# Juglans.net
KiCad netlist of a schematic drawn in Altium Designer
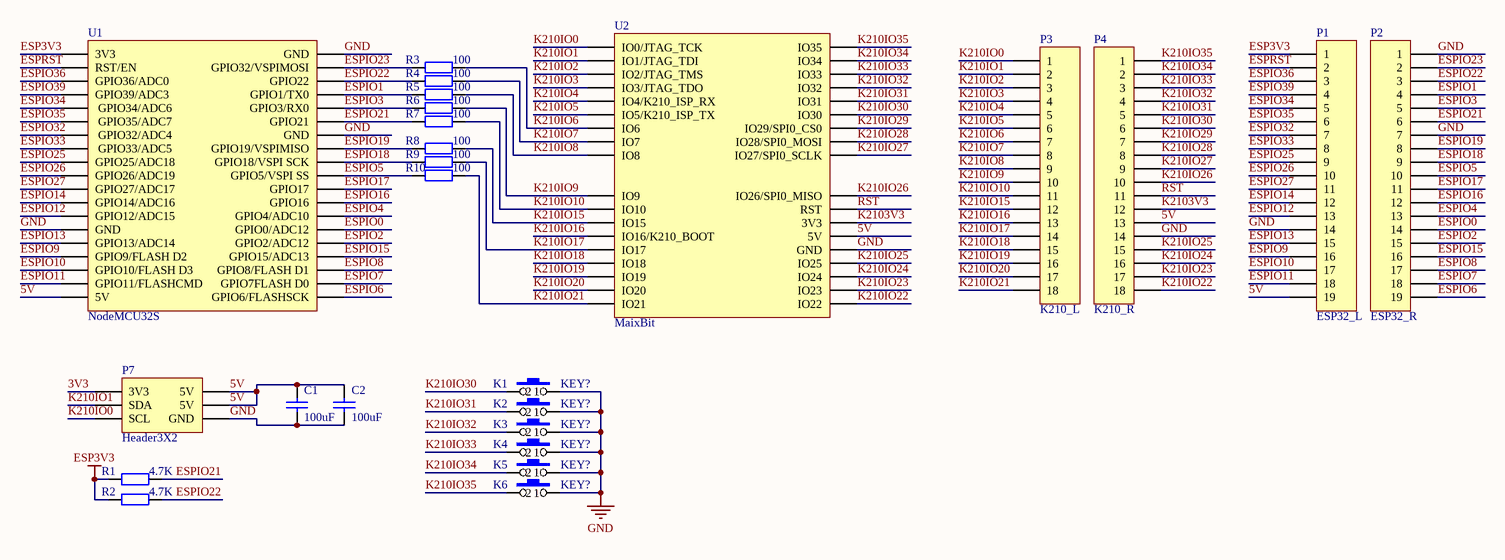
[diagram p0: Juglans.SchDoc]

(export (version "E")
  (design (tool "Eeschema 10.0.6"))
  (components
    (comp (ref "C1")
      (value "100uF")
      (footprint "C 1206_L")
      (description "Capacitor")
      (fields (field (name "Comment") "Cap") (field (name "PUBLISHER") "Altium Limited"))
      (libsource (lib "Miscellaneous Devices") (part "Cap"))
    )
    (comp (ref "C2")
      (value "100uF")
      (footprint "C 1206_L")
      (description "Capacitor")
      (fields (field (name "Comment") "Cap") (field (name "PUBLISHER") "Altium Limited"))
      (libsource (lib "Miscellaneous Devices") (part "Cap"))
    )
    (comp (ref "K1") (value "KEY?") (footprint "SW-PB2-S") (libsource (lib "Connectors") (part "SW-PB2")))
    (comp (ref "K2") (value "KEY?") (footprint "SW-PB2-S") (libsource (lib "Connectors") (part "SW-PB2")))
    (comp (ref "K3") (value "KEY?") (footprint "SW-PB2-S") (libsource (lib "Connectors") (part "SW-PB2")))
    (comp (ref "K4") (value "KEY?") (footprint "SW-PB2-S") (libsource (lib "Connectors") (part "SW-PB2")))
    (comp (ref "K5") (value "KEY?") (footprint "SW-PB2-S") (libsource (lib "Connectors") (part "SW-PB2")))
    (comp (ref "K6") (value "KEY?") (footprint "SW-PB2-S") (libsource (lib "Connectors") (part "SW-PB2")))
    (comp (ref "P1")
      (value "ESP32_L")
      (footprint "HDR1X19")
      (description "Header, 19-Pin")
      (fields (field (name "PUBLISHER") "Altium Limited"))
      (libsource (lib "") (part "Header 19_1"))
    )
    (comp (ref "P2")
      (value "ESP32_R")
      (footprint "HDR1X19")
      (description "Header, 19-Pin")
      (fields (field (name "PUBLISHER") "Altium Limited"))
      (libsource (lib "Miscellaneous Connectors") (part "Header 19"))
    )
    (comp (ref "P3")
      (value "K210_L")
      (footprint "HDR1X18")
      (description "Header, 18-Pin")
      (fields (field (name "PUBLISHER") "Altium Limited"))
      (libsource (lib "Miscellaneous Connectors") (part "Header 18"))
    )
    (comp (ref "P4")
      (value "K210_R")
      (footprint "HDR1X18")
      (description "Header, 18-Pin")
      (fields (field (name "PUBLISHER") "Altium Limited"))
      (libsource (lib "") (part "Header 18_1"))
    )
    (comp (ref "P7") (value "Header3X2") (footprint "Header3X2") (libsource (lib "Juglans") (part "H3X2")))
    (comp (ref "R1")
      (value "4.7K")
      (footprint "R 0805_M")
      (description "Resistor")
      (fields (field (name "Comment") "Res2") (field (name "PUBLISHER") "Altium Limited"))
      (libsource (lib "Miscellaneous Devices") (part "Res2"))
    )
    (comp (ref "R2")
      (value "4.7K")
      (footprint "R 0805_M")
      (description "Resistor")
      (fields (field (name "Comment") "Res2") (field (name "PUBLISHER") "Altium Limited"))
      (libsource (lib "Miscellaneous Devices") (part "Res2"))
    )
    (comp (ref "R3")
      (value "100")
      (footprint "R 0805_M")
      (description "Resistor")
      (fields (field (name "Comment") "Res2") (field (name "PUBLISHER") "Altium Limited"))
      (libsource (lib "Miscellaneous Devices") (part "Res2"))
    )
    (comp (ref "R4")
      (value "100")
      (footprint "R 0805_M")
      (description "Resistor")
      (fields (field (name "Comment") "Res2") (field (name "PUBLISHER") "Altium Limited"))
      (libsource (lib "Miscellaneous Devices") (part "Res2"))
    )
    (comp (ref "R5")
      (value "100")
      (footprint "R 0805_M")
      (description "Resistor")
      (fields (field (name "Comment") "Res2") (field (name "PUBLISHER") "Altium Limited"))
      (libsource (lib "Miscellaneous Devices") (part "Res2"))
    )
    (comp (ref "R6")
      (value "100")
      (footprint "R 0805_M")
      (description "Resistor")
      (fields (field (name "Comment") "Res2") (field (name "PUBLISHER") "Altium Limited"))
      (libsource (lib "Miscellaneous Devices") (part "Res2"))
    )
    (comp (ref "R7")
      (value "100")
      (footprint "R 0805_M")
      (description "Resistor")
      (fields (field (name "Comment") "Res2") (field (name "PUBLISHER") "Altium Limited"))
      (libsource (lib "Miscellaneous Devices") (part "Res2"))
    )
    (comp (ref "R8")
      (value "100")
      (footprint "R 0805_M")
      (description "Resistor")
      (fields (field (name "Comment") "Res2") (field (name "PUBLISHER") "Altium Limited"))
      (libsource (lib "Miscellaneous Devices") (part "Res2"))
    )
    (comp (ref "R9")
      (value "100")
      (footprint "R 0805_M")
      (description "Resistor")
      (fields (field (name "Comment") "Res2") (field (name "PUBLISHER") "Altium Limited"))
      (libsource (lib "Miscellaneous Devices") (part "Res2"))
    )
    (comp (ref "R10")
      (value "100")
      (footprint "R 0805_M")
      (description "Resistor")
      (fields (field (name "Comment") "Res2") (field (name "PUBLISHER") "Altium Limited"))
      (libsource (lib "Miscellaneous Devices") (part "Res2"))
    )
    (comp (ref "U1")
      (value "NodeMCU32S")
      (footprint "NodeMCU32S")
      (libsource (lib "Juglans") (part "NodeMCU32S"))
    )
    (comp (ref "U2") (value "MaixBit") (footprint "MaixBit") (libsource (lib "Juglans") (part "MaixBit")))
  )
  (nets
    (net (code "1") (name "/3V3") (class "Default")
      (node (ref "P7") (pin "1") (pinfunction "3V3_1") (pintype "passive"))
    )
    (net (code "2") (name "/5V") (class "Default")
      (node (ref "C1") (pin "2") (pinfunction "2_2") (pintype "passive"))
      (node (ref "C2") (pin "2") (pinfunction "2_2") (pintype "passive"))
      (node (ref "P1") (pin "19") (pinfunction "19_19") (pintype "passive"))
      (node (ref "P4") (pin "13") (pinfunction "13_13") (pintype "passive"))
      (node (ref "P7") (pin "2") (pinfunction "5V_2") (pintype "passive"))
      (node (ref "P7") (pin "4") (pinfunction "5V_4") (pintype "passive"))
      (node (ref "U1") (pin "18") (pinfunction "5V_18") (pintype "passive"))
      (node (ref "U2") (pin "23") (pinfunction "5V_23") (pintype "passive"))
    )
    (net (code "3") (name "/ESPIO0") (class "Default")
      (node (ref "P2") (pin "14") (pinfunction "14_14") (pintype "passive"))
      (node (ref "U1") (pin "24") (pinfunction "GPIO0/ADC12_24") (pintype "passive"))
    )
    (net (code "4") (name "/ESPIO1") (class "Default")
      (node (ref "P2") (pin "4") (pinfunction "4_4") (pintype "passive"))
      (node (ref "R5") (pin "2") (pinfunction "2_2") (pintype "passive"))
      (node (ref "U1") (pin "34") (pinfunction "GPIO1/TX0_34") (pintype "passive"))
    )
    (net (code "5") (name "/ESPIO2") (class "Default")
      (node (ref "P2") (pin "15") (pinfunction "15_15") (pintype "passive"))
      (node (ref "U1") (pin "23") (pinfunction "GPIO2/ADC12_23") (pintype "passive"))
    )
    (net (code "6") (name "/ESPIO3") (class "Default")
      (node (ref "P2") (pin "5") (pinfunction "5_5") (pintype "passive"))
      (node (ref "R6") (pin "2") (pinfunction "2_2") (pintype "passive"))
      (node (ref "U1") (pin "33") (pinfunction "GPIO3/RX0_33") (pintype "passive"))
    )
    (net (code "7") (name "/ESPIO4") (class "Default")
      (node (ref "P2") (pin "13") (pinfunction "13_13") (pintype "passive"))
      (node (ref "U1") (pin "25") (pinfunction "GPIO4/ADC10_25") (pintype "passive"))
    )
    (net (code "8") (name "/ESPIO5") (class "Default")
      (node (ref "P2") (pin "10") (pinfunction "10_10") (pintype "passive"))
      (node (ref "R10") (pin "2") (pinfunction "2_2") (pintype "passive"))
      (node (ref "U1") (pin "28") (pinfunction "GPIO5/VSPI_SS_28") (pintype "passive"))
    )
    (net (code "9") (name "/ESPIO6") (class "Default")
      (node (ref "P2") (pin "19") (pinfunction "19_19") (pintype "passive"))
      (node (ref "U1") (pin "19") (pinfunction "GPIO6/FLASHSCK_19") (pintype "passive"))
    )
    (net (code "10") (name "/ESPIO7") (class "Default")
      (node (ref "P2") (pin "18") (pinfunction "18_18") (pintype "passive"))
      (node (ref "U1") (pin "20") (pinfunction "GPIO7FLASH_D0_20") (pintype "passive"))
    )
    (net (code "11") (name "/ESPIO8") (class "Default")
      (node (ref "P2") (pin "17") (pinfunction "17_17") (pintype "passive"))
      (node (ref "U1") (pin "21") (pinfunction "GPIO8/FLASH_D1_21") (pintype "passive"))
    )
    (net (code "12") (name "/ESPIO9") (class "Default")
      (node (ref "P1") (pin "16") (pinfunction "16_16") (pintype "passive"))
      (node (ref "U1") (pin "15") (pinfunction "GPIO9/FLASH_D2_15") (pintype "passive"))
    )
    (net (code "13") (name "/ESPIO10") (class "Default")
      (node (ref "P1") (pin "17") (pinfunction "17_17") (pintype "passive"))
      (node (ref "U1") (pin "16") (pinfunction "GPIO10/FLASH_D3_16") (pintype "passive"))
    )
    (net (code "14") (name "/ESPIO11") (class "Default")
      (node (ref "P1") (pin "18") (pinfunction "18_18") (pintype "passive"))
      (node (ref "U1") (pin "17") (pinfunction "GPIO11/FLASHCMD_17") (pintype "passive"))
    )
    (net (code "15") (name "/ESPIO12") (class "Default")
      (node (ref "P1") (pin "13") (pinfunction "13_13") (pintype "passive"))
      (node (ref "U1") (pin "12") (pinfunction "GPIO12/ADC15_12") (pintype "passive"))
    )
    (net (code "16") (name "/ESPIO13") (class "Default")
      (node (ref "P1") (pin "15") (pinfunction "15_15") (pintype "passive"))
      (node (ref "U1") (pin "14") (pinfunction "GPIO13/ADC14_14") (pintype "passive"))
    )
    (net (code "17") (name "/ESPIO14") (class "Default")
      (node (ref "P1") (pin "12") (pinfunction "12_12") (pintype "passive"))
      (node (ref "U1") (pin "11") (pinfunction "GPIO14/ADC16_11") (pintype "passive"))
    )
    (net (code "18") (name "/ESPIO15") (class "Default")
      (node (ref "P2") (pin "16") (pinfunction "16_16") (pintype "passive"))
      (node (ref "U1") (pin "22") (pinfunction "GPIO15/ADC13_22") (pintype "passive"))
    )
    (net (code "19") (name "/ESPIO16") (class "Default")
      (node (ref "P2") (pin "12") (pinfunction "12_12") (pintype "passive"))
      (node (ref "U1") (pin "26") (pinfunction "GPIO16_26") (pintype "passive"))
    )
    (net (code "20") (name "/ESPIO17") (class "Default")
      (node (ref "P2") (pin "11") (pinfunction "11_11") (pintype "passive"))
      (node (ref "U1") (pin "27") (pinfunction "GPIO17_27") (pintype "passive"))
    )
    (net (code "21") (name "/ESPIO18") (class "Default")
      (node (ref "P2") (pin "9") (pinfunction "9_9") (pintype "passive"))
      (node (ref "R9") (pin "2") (pinfunction "2_2") (pintype "passive"))
      (node (ref "U1") (pin "29") (pinfunction "GPIO18/VSPI_SCK_29") (pintype "passive"))
    )
    (net (code "22") (name "/ESPIO19") (class "Default")
      (node (ref "P2") (pin "8") (pinfunction "8_8") (pintype "passive"))
      (node (ref "R8") (pin "2") (pinfunction "2_2") (pintype "passive"))
      (node (ref "U1") (pin "30") (pinfunction "GPIO19/VSPIMISO_30") (pintype "passive"))
    )
    (net (code "23") (name "/ESPIO21") (class "Default")
      (node (ref "P2") (pin "6") (pinfunction "6_6") (pintype "passive"))
      (node (ref "R1") (pin "1") (pinfunction "1_1") (pintype "passive"))
      (node (ref "R7") (pin "2") (pinfunction "2_2") (pintype "passive"))
      (node (ref "U1") (pin "32") (pinfunction "GPIO21_32") (pintype "passive"))
    )
    (net (code "24") (name "/ESPIO22") (class "Default")
      (node (ref "P2") (pin "3") (pinfunction "3_3") (pintype "passive"))
      (node (ref "R2") (pin "1") (pinfunction "1_1") (pintype "passive"))
      (node (ref "R4") (pin "2") (pinfunction "2_2") (pintype "passive"))
      (node (ref "U1") (pin "35") (pinfunction "GPIO22_35") (pintype "passive"))
    )
    (net (code "25") (name "/ESPIO23") (class "Default")
      (node (ref "P2") (pin "2") (pinfunction "2_2") (pintype "passive"))
      (node (ref "R3") (pin "2") (pinfunction "2_2") (pintype "passive"))
      (node (ref "U1") (pin "36") (pinfunction "GPIO32/VSPIMOSI_36") (pintype "passive"))
    )
    (net (code "26") (name "/ESPIO25") (class "Default")
      (node (ref "P1") (pin "9") (pinfunction "9_9") (pintype "passive"))
      (node (ref "U1") (pin "8") (pinfunction "GPIO25/ADC18_8") (pintype "passive"))
    )
    (net (code "27") (name "/ESPIO26") (class "Default")
      (node (ref "P1") (pin "10") (pinfunction "10_10") (pintype "passive"))
      (node (ref "U1") (pin "9") (pinfunction "GPIO26/ADC19_9") (pintype "passive"))
    )
    (net (code "28") (name "/ESPIO27") (class "Default")
      (node (ref "P1") (pin "11") (pinfunction "11_11") (pintype "passive"))
      (node (ref "U1") (pin "10") (pinfunction "GPIO27/ADC17_10") (pintype "passive"))
    )
    (net (code "29") (name "/ESPIO32") (class "Default")
      (node (ref "P1") (pin "7") (pinfunction "7_7") (pintype "passive"))
      (node (ref "U1") (pin "6") (pinfunction "_GPIO32/ADC4_6") (pintype "passive"))
    )
    (net (code "30") (name "/ESPIO33") (class "Default")
      (node (ref "P1") (pin "8") (pinfunction "8_8") (pintype "passive"))
      (node (ref "U1") (pin "7") (pinfunction "_GPIO33/ADC5_7") (pintype "passive"))
    )
    (net (code "31") (name "/ESPIO34") (class "Default")
      (node (ref "P1") (pin "5") (pinfunction "5_5") (pintype "passive"))
      (node (ref "U1") (pin "4") (pinfunction "_GPIO34/ADC6_4") (pintype "passive"))
    )
    (net (code "32") (name "/ESPIO35") (class "Default")
      (node (ref "P1") (pin "6") (pinfunction "6_6") (pintype "passive"))
      (node (ref "U1") (pin "5") (pinfunction "_GPIO35/ADC7_5") (pintype "passive"))
    )
    (net (code "33") (name "/ESPIO36") (class "Default")
      (node (ref "P1") (pin "3") (pinfunction "3_3") (pintype "passive"))
      (node (ref "U1") (pin "2") (pinfunction "GPIO36/ADC0_2") (pintype "passive"))
    )
    (net (code "34") (name "/ESPIO39") (class "Default")
      (node (ref "P1") (pin "4") (pinfunction "4_4") (pintype "passive"))
      (node (ref "U1") (pin "3") (pinfunction "GPIO39/ADC3_3") (pintype "passive"))
    )
    (net (code "35") (name "/ESPRST") (class "Default")
      (node (ref "P1") (pin "2") (pinfunction "2_2") (pintype "passive"))
      (node (ref "U1") (pin "1") (pinfunction "RST/EN_1") (pintype "passive"))
    )
    (net (code "36") (name "/K210IO0") (class "Default")
      (node (ref "P3") (pin "1") (pinfunction "1_1") (pintype "passive"))
      (node (ref "P7") (pin "5") (pinfunction "SCL_5") (pintype "passive"))
      (node (ref "U2") (pin "0") (pinfunction "IO0/JTAG_TCK_0") (pintype "passive"))
    )
    (net (code "37") (name "/K210IO1") (class "Default")
      (node (ref "P3") (pin "2") (pinfunction "2_2") (pintype "passive"))
      (node (ref "P7") (pin "3") (pinfunction "SDA_3") (pintype "passive"))
      (node (ref "U2") (pin "1") (pinfunction "IO1/JTAG_TDI_1") (pintype "passive"))
    )
    (net (code "38") (name "/K210IO2") (class "Default")
      (node (ref "P3") (pin "3") (pinfunction "3_3") (pintype "passive"))
      (node (ref "U2") (pin "2") (pinfunction "IO2/JTAG_TMS_2") (pintype "passive"))
    )
    (net (code "39") (name "/K210IO3") (class "Default")
      (node (ref "P3") (pin "4") (pinfunction "4_4") (pintype "passive"))
      (node (ref "U2") (pin "3") (pinfunction "IO3/JTAG_TDO_3") (pintype "passive"))
    )
    (net (code "40") (name "/K210IO4") (class "Default")
      (node (ref "P3") (pin "5") (pinfunction "5_5") (pintype "passive"))
      (node (ref "U2") (pin "4") (pinfunction "IO4/K210_ISP_RX_4") (pintype "passive"))
    )
    (net (code "41") (name "/K210IO5") (class "Default")
      (node (ref "P3") (pin "6") (pinfunction "6_6") (pintype "passive"))
      (node (ref "U2") (pin "5") (pinfunction "IO5/K210_ISP_TX_5") (pintype "passive"))
    )
    (net (code "42") (name "/K210IO6") (class "Default")
      (node (ref "P3") (pin "7") (pinfunction "7_7") (pintype "passive"))
      (node (ref "R3") (pin "1") (pinfunction "1_1") (pintype "passive"))
      (node (ref "U2") (pin "6") (pinfunction "IO6_6") (pintype "passive"))
    )
    (net (code "43") (name "/K210IO7") (class "Default")
      (node (ref "P3") (pin "8") (pinfunction "8_8") (pintype "passive"))
      (node (ref "R4") (pin "1") (pinfunction "1_1") (pintype "passive"))
      (node (ref "U2") (pin "7") (pinfunction "IO7_7") (pintype "passive"))
    )
    (net (code "44") (name "/K210IO8") (class "Default")
      (node (ref "P3") (pin "9") (pinfunction "9_9") (pintype "passive"))
      (node (ref "R5") (pin "1") (pinfunction "1_1") (pintype "passive"))
      (node (ref "U2") (pin "8") (pinfunction "IO8_8") (pintype "passive"))
    )
    (net (code "45") (name "/K210IO9") (class "Default")
      (node (ref "P3") (pin "10") (pinfunction "10_10") (pintype "passive"))
      (node (ref "R6") (pin "1") (pinfunction "1_1") (pintype "passive"))
      (node (ref "U2") (pin "9") (pinfunction "IO9_9") (pintype "passive"))
    )
    (net (code "46") (name "/K210IO10") (class "Default")
      (node (ref "P3") (pin "11") (pinfunction "11_11") (pintype "passive"))
      (node (ref "R7") (pin "1") (pinfunction "1_1") (pintype "passive"))
      (node (ref "U2") (pin "10") (pinfunction "IO10_10") (pintype "passive"))
    )
    (net (code "47") (name "/K210IO15") (class "Default")
      (node (ref "P3") (pin "12") (pinfunction "12_12") (pintype "passive"))
      (node (ref "R8") (pin "1") (pinfunction "1_1") (pintype "passive"))
      (node (ref "U2") (pin "11") (pinfunction "IO15_11") (pintype "passive"))
    )
    (net (code "48") (name "/K210IO16") (class "Default")
      (node (ref "P3") (pin "13") (pinfunction "13_13") (pintype "passive"))
      (node (ref "U2") (pin "12") (pinfunction "IO16/K210_BOOT_12") (pintype "passive"))
    )
    (net (code "49") (name "/K210IO17") (class "Default")
      (node (ref "P3") (pin "14") (pinfunction "14_14") (pintype "passive"))
      (node (ref "R9") (pin "1") (pinfunction "1_1") (pintype "passive"))
      (node (ref "U2") (pin "13") (pinfunction "IO17_13") (pintype "passive"))
    )
    (net (code "50") (name "/K210IO18") (class "Default")
      (node (ref "P3") (pin "15") (pinfunction "15_15") (pintype "passive"))
      (node (ref "U2") (pin "14") (pinfunction "IO18_14") (pintype "passive"))
    )
    (net (code "51") (name "/K210IO19") (class "Default")
      (node (ref "P3") (pin "16") (pinfunction "16_16") (pintype "passive"))
      (node (ref "U2") (pin "15") (pinfunction "IO19_15") (pintype "passive"))
    )
    (net (code "52") (name "/K210IO20") (class "Default")
      (node (ref "P3") (pin "17") (pinfunction "17_17") (pintype "passive"))
      (node (ref "U2") (pin "16") (pinfunction "IO20_16") (pintype "passive"))
    )
    (net (code "53") (name "/K210IO21") (class "Default")
      (node (ref "P3") (pin "18") (pinfunction "18_18") (pintype "passive"))
      (node (ref "R10") (pin "1") (pinfunction "1_1") (pintype "passive"))
      (node (ref "U2") (pin "17") (pinfunction "IO21_17") (pintype "passive"))
    )
    (net (code "54") (name "/K210IO22") (class "Default")
      (node (ref "P4") (pin "18") (pinfunction "18_18") (pintype "passive"))
      (node (ref "U2") (pin "18") (pinfunction "IO22_18") (pintype "passive"))
    )
    (net (code "55") (name "/K210IO23") (class "Default")
      (node (ref "P4") (pin "17") (pinfunction "17_17") (pintype "passive"))
      (node (ref "U2") (pin "19") (pinfunction "IO23_19") (pintype "passive"))
    )
    (net (code "56") (name "/K210IO24") (class "Default")
      (node (ref "P4") (pin "16") (pinfunction "16_16") (pintype "passive"))
      (node (ref "U2") (pin "20") (pinfunction "IO24_20") (pintype "passive"))
    )
    (net (code "57") (name "/K210IO25") (class "Default")
      (node (ref "P4") (pin "15") (pinfunction "15_15") (pintype "passive"))
      (node (ref "U2") (pin "21") (pinfunction "IO25_21") (pintype "passive"))
    )
    (net (code "58") (name "/K210IO26") (class "Default")
      (node (ref "P4") (pin "10") (pinfunction "10_10") (pintype "passive"))
      (node (ref "U2") (pin "26") (pinfunction "IO26/SPI0_MISO_26") (pintype "passive"))
    )
    (net (code "59") (name "/K210IO27") (class "Default")
      (node (ref "P4") (pin "9") (pinfunction "9_9") (pintype "passive"))
      (node (ref "U2") (pin "27") (pinfunction "IO27/SPI0_SCLK_27") (pintype "passive"))
    )
    (net (code "60") (name "/K210IO28") (class "Default")
      (node (ref "P4") (pin "8") (pinfunction "8_8") (pintype "passive"))
      (node (ref "U2") (pin "28") (pinfunction "IO28/SPI0_MOSI_28") (pintype "passive"))
    )
    (net (code "61") (name "/K210IO29") (class "Default")
      (node (ref "P4") (pin "7") (pinfunction "7_7") (pintype "passive"))
      (node (ref "U2") (pin "29") (pinfunction "IO29/SPI0_CS0_29") (pintype "passive"))
    )
    (net (code "62") (name "/K210IO30") (class "Default")
      (node (ref "K1") (pin "1") (pinfunction "1_1") (pintype "passive"))
      (node (ref "P4") (pin "6") (pinfunction "6_6") (pintype "passive"))
      (node (ref "U2") (pin "30") (pinfunction "IO30_30") (pintype "passive"))
    )
    (net (code "63") (name "/K210IO31") (class "Default")
      (node (ref "K2") (pin "1") (pinfunction "1_1") (pintype "passive"))
      (node (ref "P4") (pin "5") (pinfunction "5_5") (pintype "passive"))
      (node (ref "U2") (pin "31") (pinfunction "IO31_31") (pintype "passive"))
    )
    (net (code "64") (name "/K210IO32") (class "Default")
      (node (ref "K3") (pin "1") (pinfunction "1_1") (pintype "passive"))
      (node (ref "P4") (pin "4") (pinfunction "4_4") (pintype "passive"))
      (node (ref "U2") (pin "32") (pinfunction "IO32_32") (pintype "passive"))
    )
    (net (code "65") (name "/K210IO33") (class "Default")
      (node (ref "K4") (pin "1") (pinfunction "1_1") (pintype "passive"))
      (node (ref "P4") (pin "3") (pinfunction "3_3") (pintype "passive"))
      (node (ref "U2") (pin "33") (pinfunction "IO33_33") (pintype "passive"))
    )
    (net (code "66") (name "/K210IO34") (class "Default")
      (node (ref "K5") (pin "1") (pinfunction "1_1") (pintype "passive"))
      (node (ref "P4") (pin "2") (pinfunction "2_2") (pintype "passive"))
      (node (ref "U2") (pin "34") (pinfunction "IO34_34") (pintype "passive"))
    )
    (net (code "67") (name "/K210IO35") (class "Default")
      (node (ref "K6") (pin "1") (pinfunction "1_1") (pintype "passive"))
      (node (ref "P4") (pin "1") (pinfunction "1_1") (pintype "passive"))
      (node (ref "U2") (pin "35") (pinfunction "IO35_35") (pintype "passive"))
    )
    (net (code "68") (name "/K2103V3") (class "Default")
      (node (ref "P4") (pin "12") (pinfunction "12_12") (pintype "passive"))
      (node (ref "U2") (pin "24") (pinfunction "3V3_24") (pintype "passive"))
    )
    (net (code "69") (name "/RST") (class "Default")
      (node (ref "P4") (pin "11") (pinfunction "11_11") (pintype "passive"))
      (node (ref "U2") (pin "25") (pinfunction "RST_25") (pintype "passive"))
    )
    (net (code "70") (name "ESP3V3") (class "Default")
      (node (ref "P1") (pin "1") (pinfunction "1_1") (pintype "passive"))
      (node (ref "R1") (pin "2") (pinfunction "2_2") (pintype "passive"))
      (node (ref "R2") (pin "2") (pinfunction "2_2") (pintype "passive"))
      (node (ref "U1") (pin "0") (pinfunction "3V3_0") (pintype "passive"))
    )
    (net (code "71") (name "GND") (class "Default")
      (node (ref "C1") (pin "1") (pinfunction "1_1") (pintype "passive"))
      (node (ref "C2") (pin "1") (pinfunction "1_1") (pintype "passive"))
      (node (ref "K1") (pin "2") (pinfunction "2_2") (pintype "passive"))
      (node (ref "K2") (pin "2") (pinfunction "2_2") (pintype "passive"))
      (node (ref "K3") (pin "2") (pinfunction "2_2") (pintype "passive"))
      (node (ref "K4") (pin "2") (pinfunction "2_2") (pintype "passive"))
      (node (ref "K5") (pin "2") (pinfunction "2_2") (pintype "passive"))
      (node (ref "K6") (pin "2") (pinfunction "2_2") (pintype "passive"))
      (node (ref "P1") (pin "14") (pinfunction "14_14") (pintype "passive"))
      (node (ref "P2") (pin "1") (pinfunction "1_1") (pintype "passive"))
      (node (ref "P2") (pin "7") (pinfunction "7_7") (pintype "passive"))
      (node (ref "P4") (pin "14") (pinfunction "14_14") (pintype "passive"))
      (node (ref "P7") (pin "6") (pinfunction "GND_6") (pintype "passive"))
      (node (ref "U1") (pin "13") (pinfunction "GND_13") (pintype "passive"))
      (node (ref "U1") (pin "31") (pinfunction "GND_31") (pintype "passive"))
      (node (ref "U1") (pin "37") (pinfunction "GND_37") (pintype "passive"))
      (node (ref "U2") (pin "22") (pinfunction "GND_22") (pintype "passive"))
    )
  )
)
